# dev-board.net
KiCad netlist of a schematic drawn in EAGLE
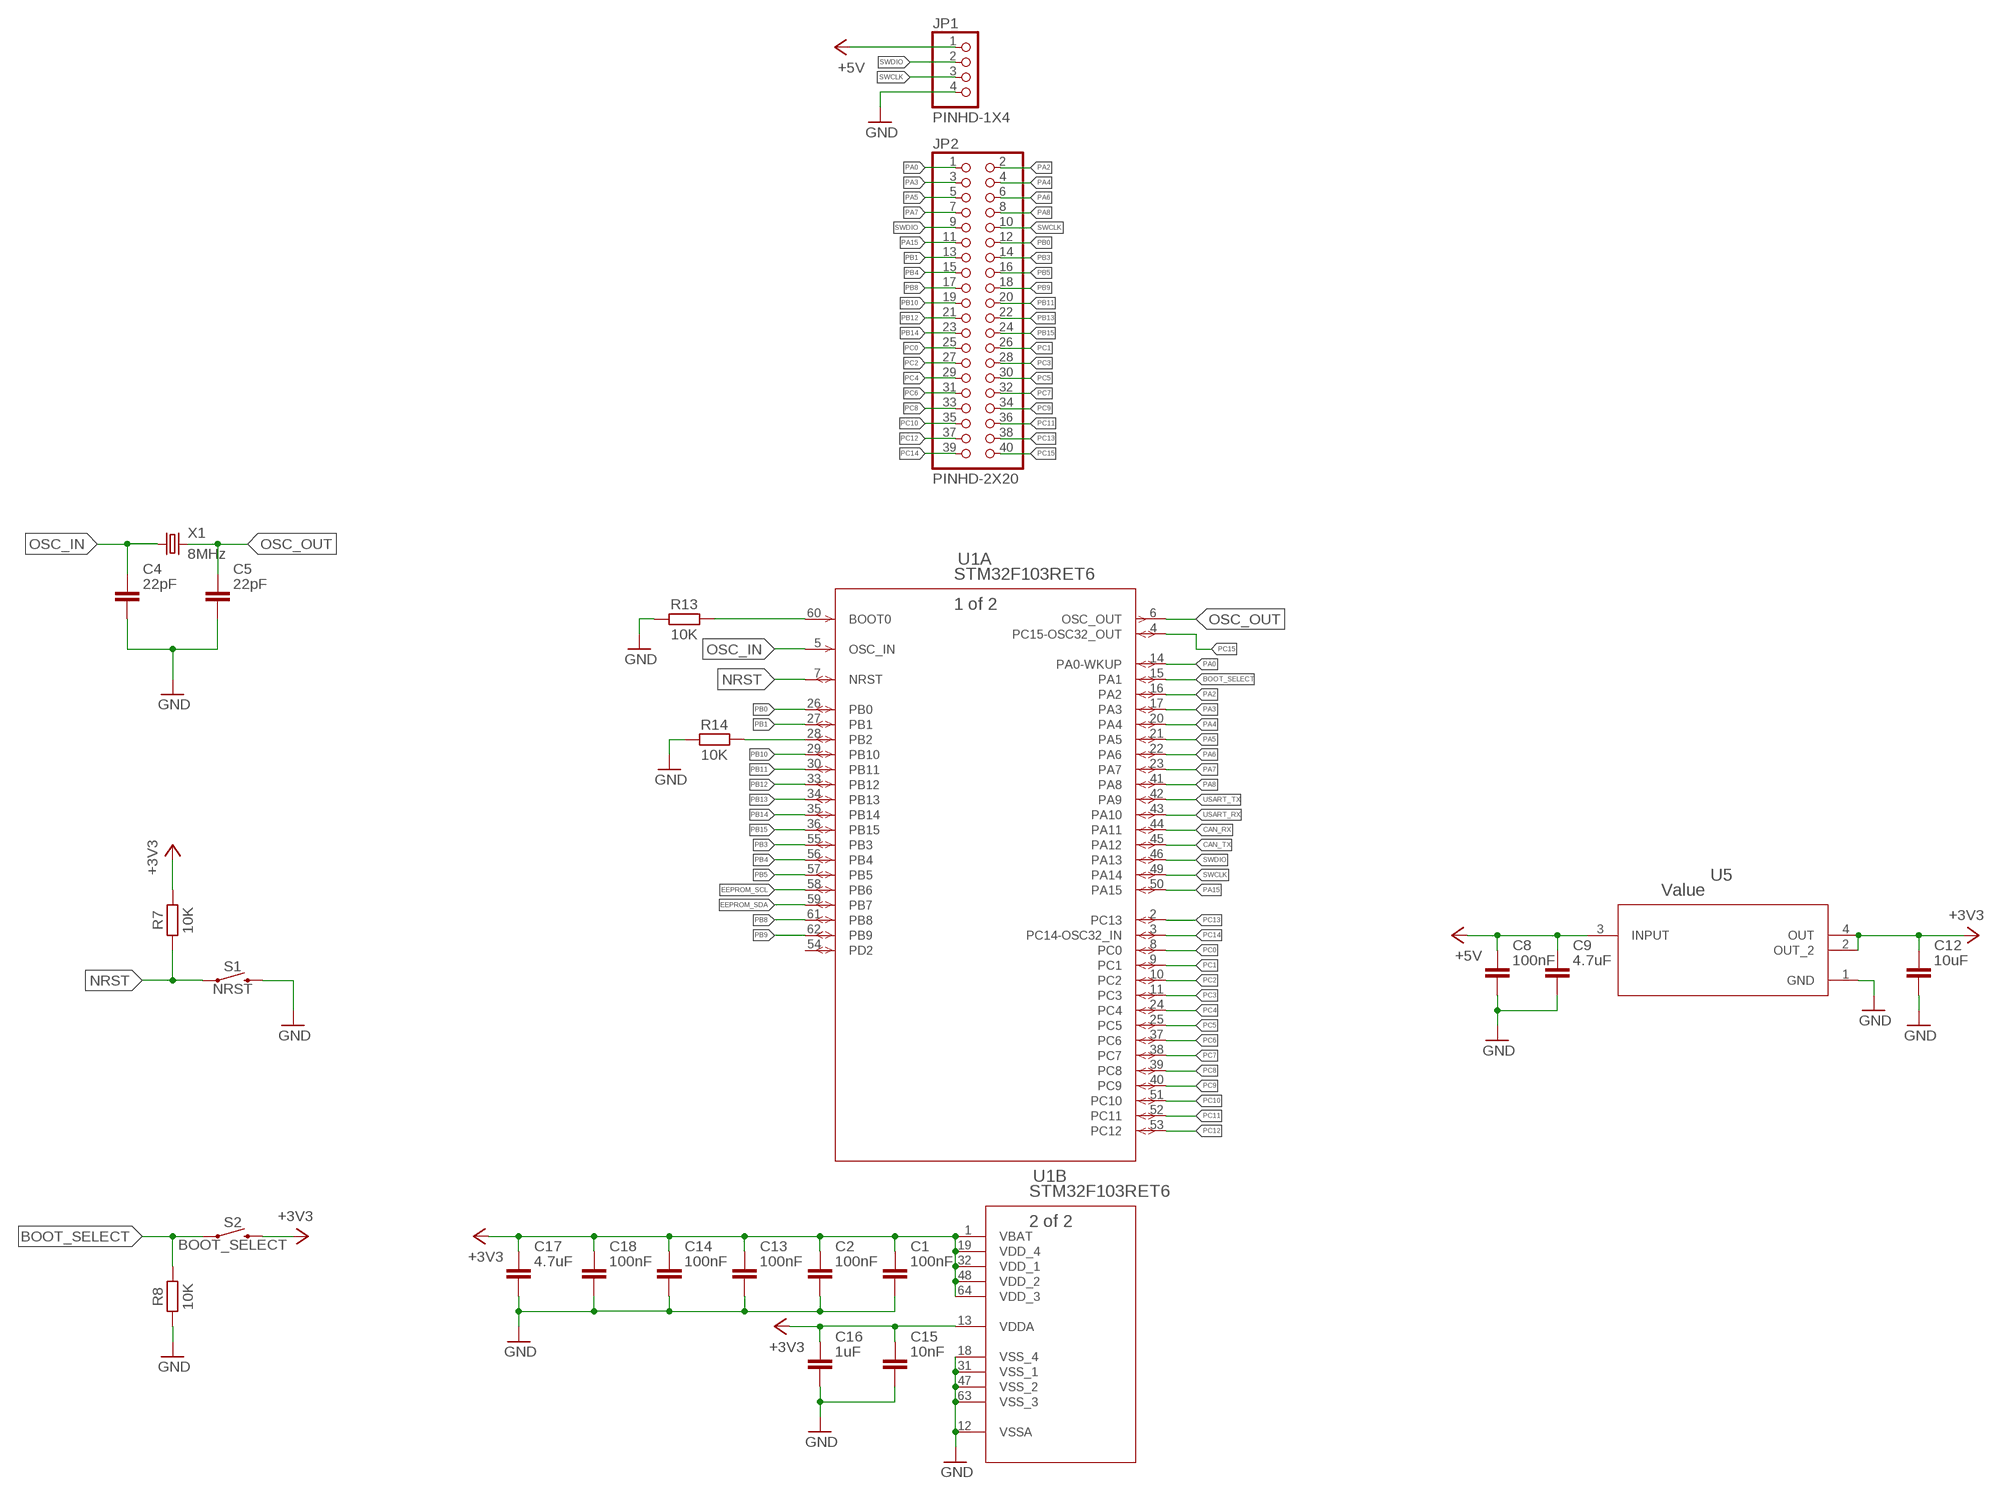
[diagram p0: schematic, sheet 1, part 1 of 2]
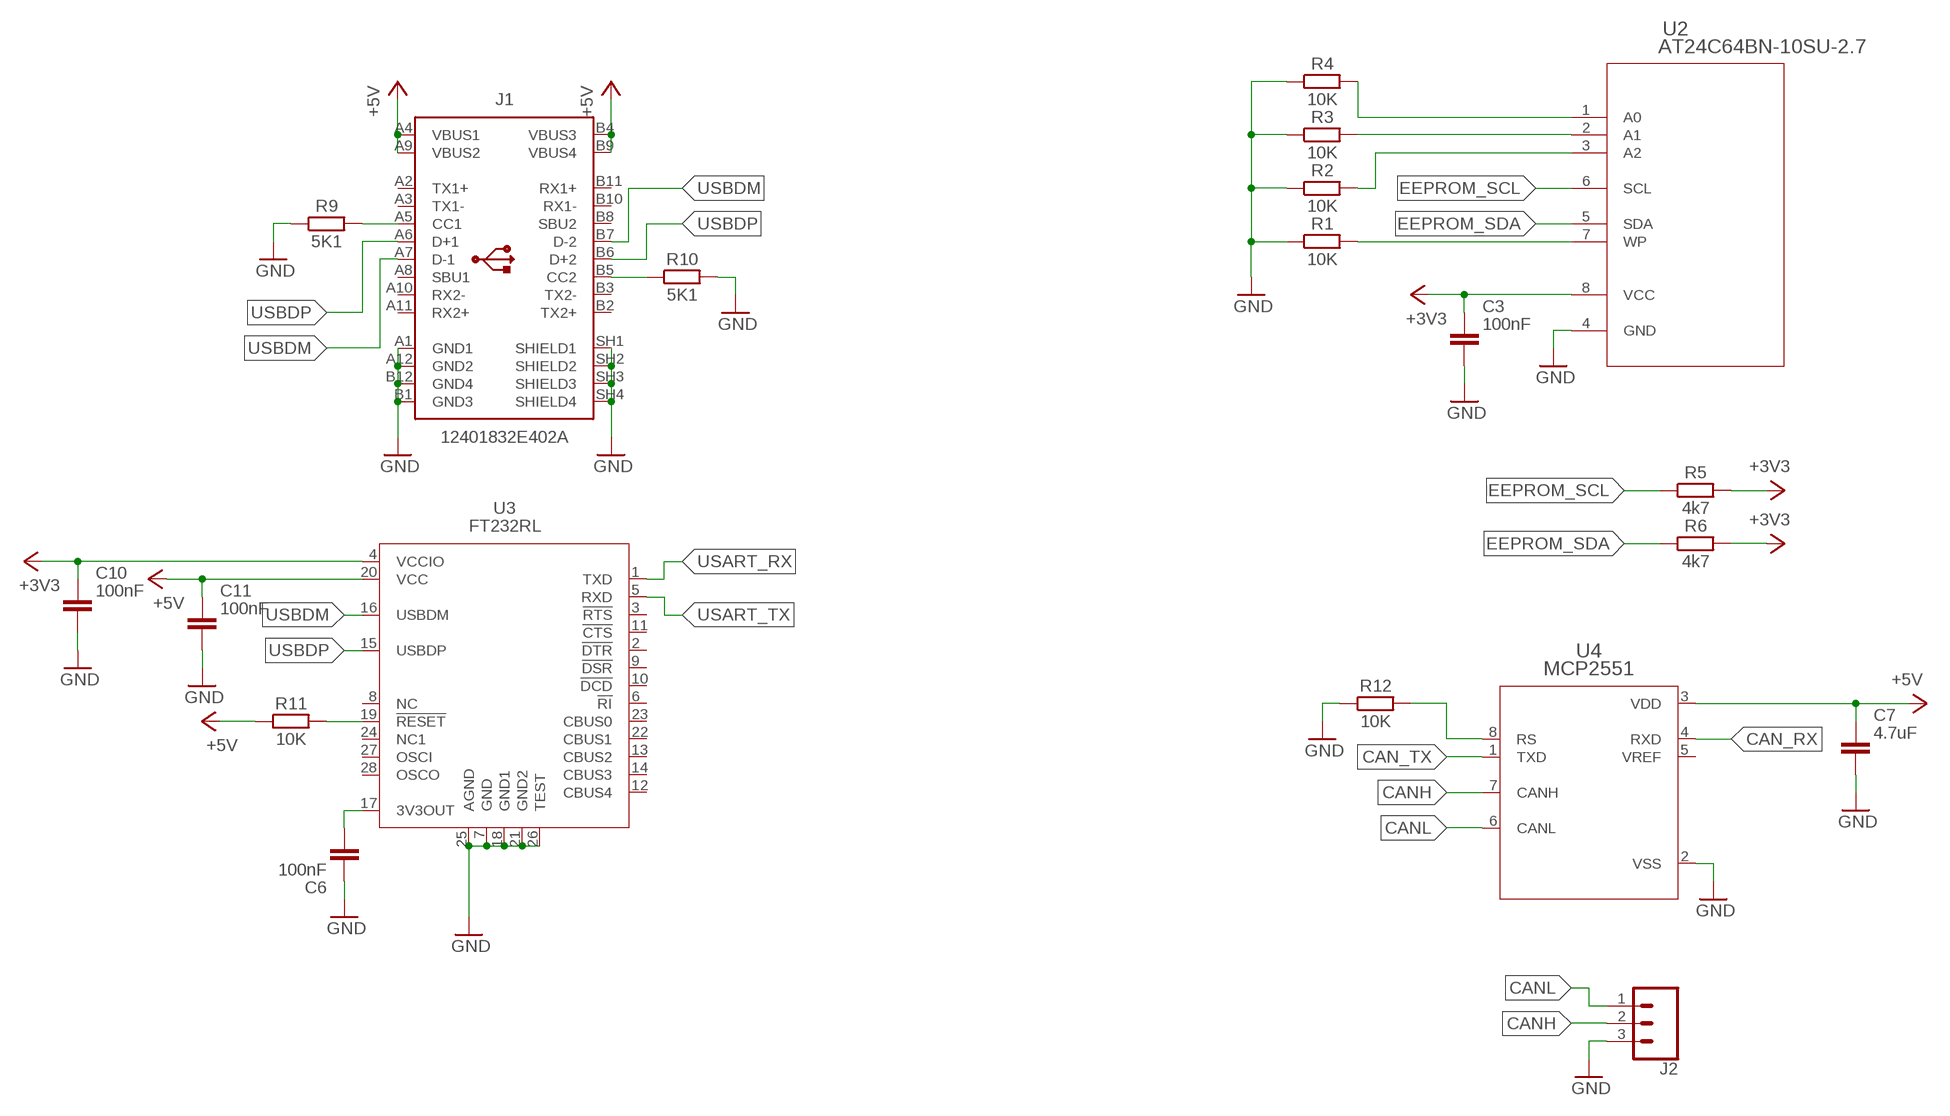
[diagram p1: schematic, sheet 1, part 2 of 2]

(export (version "E")
  (design (tool "Eeschema 10.0.6"))
  (components
    (comp (ref "C1")
      (value "100nF")
      (footprint "eagle-import:CAPC2012X110")
      (libsource (lib "eagle-import") (part "CCHIP-0805(2012-METRIC)_"))
    )
    (comp (ref "C2")
      (value "100nF")
      (footprint "eagle-import:CAPC2012X110")
      (libsource (lib "eagle-import") (part "CCHIP-0805(2012-METRIC)_"))
    )
    (comp (ref "C3")
      (value "100nF")
      (footprint "eagle-import:CAPC2012X110")
      (libsource (lib "eagle-import") (part "CCHIP-0805(2012-METRIC)_"))
    )
    (comp (ref "C4")
      (value "22pF")
      (footprint "eagle-import:CAPC2012X110")
      (libsource (lib "eagle-import") (part "CCHIP-0805(2012-METRIC)_"))
    )
    (comp (ref "C5")
      (value "22pF")
      (footprint "eagle-import:CAPC2012X110")
      (libsource (lib "eagle-import") (part "CCHIP-0805(2012-METRIC)_"))
    )
    (comp (ref "C6")
      (value "100nF")
      (footprint "eagle-import:CAPC2012X110")
      (libsource (lib "eagle-import") (part "CCHIP-0805(2012-METRIC)_"))
    )
    (comp (ref "C7")
      (value "4.7uF")
      (footprint "eagle-import:CAPC2012X110")
      (libsource (lib "eagle-import") (part "CCHIP-0805(2012-METRIC)_"))
    )
    (comp (ref "C8")
      (value "100nF")
      (footprint "eagle-import:CAPC2012X110")
      (libsource (lib "eagle-import") (part "CCHIP-0805(2012-METRIC)_"))
    )
    (comp (ref "C9")
      (value "4.7uF")
      (footprint "eagle-import:CAPC2012X110")
      (libsource (lib "eagle-import") (part "CCHIP-0805(2012-METRIC)_"))
    )
    (comp (ref "C10")
      (value "100nF")
      (footprint "eagle-import:CAPC2012X110")
      (libsource (lib "eagle-import") (part "CCHIP-0805(2012-METRIC)_"))
    )
    (comp (ref "C11")
      (value "100nF")
      (footprint "eagle-import:CAPC2012X110")
      (libsource (lib "eagle-import") (part "CCHIP-0805(2012-METRIC)_"))
    )
    (comp (ref "C12")
      (value "10uF")
      (footprint "eagle-import:CAPC2012X110")
      (libsource (lib "eagle-import") (part "CCHIP-0805(2012-METRIC)_"))
    )
    (comp (ref "C13")
      (value "100nF")
      (footprint "eagle-import:CAPC2012X110")
      (libsource (lib "eagle-import") (part "CCHIP-0805(2012-METRIC)_"))
    )
    (comp (ref "C14")
      (value "100nF")
      (footprint "eagle-import:CAPC2012X110")
      (libsource (lib "eagle-import") (part "CCHIP-0805(2012-METRIC)_"))
    )
    (comp (ref "C15")
      (value "10nF")
      (footprint "eagle-import:CAPC2012X110")
      (libsource (lib "eagle-import") (part "CCHIP-0805(2012-METRIC)_"))
    )
    (comp (ref "C16")
      (value "1uF")
      (footprint "eagle-import:CAPC2012X110")
      (libsource (lib "eagle-import") (part "CCHIP-0805(2012-METRIC)_"))
    )
    (comp (ref "C17")
      (value "4.7uF")
      (footprint "eagle-import:CAPC2012X110")
      (libsource (lib "eagle-import") (part "CCHIP-0805(2012-METRIC)_"))
    )
    (comp (ref "C18")
      (value "100nF")
      (footprint "eagle-import:CAPC2012X110")
      (libsource (lib "eagle-import") (part "CCHIP-0805(2012-METRIC)_"))
    )
    (comp (ref "J1")
      (value "12401832E402A")
      (footprint "eagle-import:12401832E402A")
      (fields (field (name "MANUFACTURER") "Amphenol ICC"))
      (libsource (lib "eagle-import") (part "12401832E402A"))
    )
    (comp (ref "J2")
      (value "CONN_03-SCREW-5MM")
      (footprint "eagle-import:SCREWTERMINAL-5MM-3")
      (libsource (lib "eagle-import") (part "CONN_03-SCREW-5MM"))
    )
    (comp (ref "JP1")
      (value "PINHD-1X4")
      (footprint "eagle-import:1X04")
      (libsource (lib "eagle-import") (part "PINHD-1X4"))
    )
    (comp (ref "JP2")
      (value "PINHD-2X20")
      (footprint "eagle-import:2X20")
      (libsource (lib "eagle-import") (part "PINHD-2X20"))
    )
    (comp (ref "R1")
      (value "10K")
      (footprint "eagle-import:RESC2012X65")
      (libsource (lib "eagle-import") (part "RCHIP-0805(2012-METRIC)_"))
    )
    (comp (ref "R2")
      (value "10K")
      (footprint "eagle-import:RESC2012X65")
      (libsource (lib "eagle-import") (part "RCHIP-0805(2012-METRIC)_"))
    )
    (comp (ref "R3")
      (value "10K")
      (footprint "eagle-import:RESC2012X65")
      (libsource (lib "eagle-import") (part "RCHIP-0805(2012-METRIC)_"))
    )
    (comp (ref "R4")
      (value "10K")
      (footprint "eagle-import:RESC2012X65")
      (libsource (lib "eagle-import") (part "RCHIP-0805(2012-METRIC)_"))
    )
    (comp (ref "R5")
      (value "4k7")
      (footprint "eagle-import:RESC2012X65")
      (libsource (lib "eagle-import") (part "RCHIP-0805(2012-METRIC)_"))
    )
    (comp (ref "R6")
      (value "4k7")
      (footprint "eagle-import:RESC2012X65")
      (libsource (lib "eagle-import") (part "RCHIP-0805(2012-METRIC)_"))
    )
    (comp (ref "R7")
      (value "10K")
      (footprint "eagle-import:RESC2012X65")
      (libsource (lib "eagle-import") (part "RCHIP-0805(2012-METRIC)_"))
    )
    (comp (ref "R8")
      (value "10K")
      (footprint "eagle-import:RESC2012X65")
      (libsource (lib "eagle-import") (part "RCHIP-0805(2012-METRIC)_"))
    )
    (comp (ref "R9")
      (value "5K1")
      (footprint "eagle-import:RESC2012X65")
      (libsource (lib "eagle-import") (part "RCHIP-0805(2012-METRIC)_"))
    )
    (comp (ref "R10")
      (value "5K1")
      (footprint "eagle-import:RESC2012X65")
      (libsource (lib "eagle-import") (part "RCHIP-0805(2012-METRIC)_"))
    )
    (comp (ref "R11")
      (value "10K")
      (footprint "eagle-import:RESC2012X65")
      (libsource (lib "eagle-import") (part "RCHIP-0805(2012-METRIC)_"))
    )
    (comp (ref "R12")
      (value "10K")
      (footprint "eagle-import:RESC2012X65")
      (libsource (lib "eagle-import") (part "RCHIP-0805(2012-METRIC)_"))
    )
    (comp (ref "R13")
      (value "10K")
      (footprint "eagle-import:RESC2012X65")
      (libsource (lib "eagle-import") (part "RCHIP-0805(2012-METRIC)_"))
    )
    (comp (ref "R14")
      (value "10K")
      (footprint "eagle-import:RESC2012X65")
      (libsource (lib "eagle-import") (part "RCHIP-0805(2012-METRIC)_"))
    )
    (comp (ref "S1")
      (value "NRST")
      (footprint "eagle-import:TACTILE_SWITCH_SMD_6.0X3.5MM")
      (libsource (lib "eagle-import") (part "MOMENTARY-SWITCH-SPST-SMD-6.0X3.5MM"))
    )
    (comp (ref "S2")
      (value "BOOT_SELECT")
      (footprint "eagle-import:TACTILE_SWITCH_SMD_6.0X3.5MM")
      (libsource (lib "eagle-import") (part "MOMENTARY-SWITCH-SPST-SMD-6.0X3.5MM"))
    )
    (comp (ref "U1")
      (value "STM32F103RET6")
      (footprint "eagle-import:LQFP64-10X10MM")
      (fields (field (name "COPYRIGHT") "Copyright (C) 2018 Accelerated Designs. All rights reserved"))
      (libsource (lib "eagle-import") (part "STM32F103RET6"))
    )
    (comp (ref "U2")
      (value "AT24C64BN-10SU-2.7")
      (footprint "eagle-import:8S1_ATM")
      (libsource (lib "eagle-import") (part "AT24C64BN-10SU-2.7"))
    )
    (comp (ref "U3")
      (value "FT232RL")
      (footprint "eagle-import:SSOP28")
      (fields (field (name "MANUFACTURER") "FTDI Chip"))
      (libsource (lib "eagle-import") (part "FT232RL_SSOP"))
    )
    (comp (ref "U4")
      (value "MCP2551")
      (footprint "eagle-import:SOIC127P599X175-8")
      (fields (field (name "MANUFACTURER") "Microchip") (field (name "MPN") "MCP2551-E/SN"))
      (libsource (lib "eagle-import") (part "MCP2551_SOIC"))
    )
    (comp (ref "U5")
      (value "Value")
      (footprint "eagle-import:DCY0004A_N")
      (fields
        (field (name "MANUFACTURER") "Texas Instruments")
        (field (name "PARTNUMBER") "LM1117IMP-3.3/NOPB")
      )
      (libsource (lib "eagle-import") (part "LM1117IMP-3.3/NOPB"))
    )
    (comp (ref "X1")
      (value "8MHz")
      (footprint "eagle-import:HC49-4-HSMX")
      (libsource (lib "eagle-import") (part "CRYSTALS-NOGND-4-HSMX"))
    )
  )
  (nets
    (net (code "1") (name "+3V3") (class "Default")
      (node (ref "C1") (pin "1") (pinfunction "1_1") (pintype "passive"))
      (node (ref "C10") (pin "1") (pinfunction "1_1") (pintype "passive"))
      (node (ref "C12") (pin "1") (pinfunction "1_1") (pintype "passive"))
      (node (ref "C13") (pin "1") (pinfunction "1_1") (pintype "passive"))
      (node (ref "C14") (pin "1") (pinfunction "1_1") (pintype "passive"))
      (node (ref "C15") (pin "1") (pinfunction "1_1") (pintype "passive"))
      (node (ref "C16") (pin "1") (pinfunction "1_1") (pintype "passive"))
      (node (ref "C17") (pin "1") (pinfunction "1_1") (pintype "passive"))
      (node (ref "C18") (pin "1") (pinfunction "1_1") (pintype "passive"))
      (node (ref "C2") (pin "1") (pinfunction "1_1") (pintype "passive"))
      (node (ref "C3") (pin "1") (pinfunction "1_1") (pintype "passive"))
      (node (ref "R5") (pin "2") (pinfunction "2_2") (pintype "passive"))
      (node (ref "R6") (pin "2") (pinfunction "2_2") (pintype "passive"))
      (node (ref "R7") (pin "2") (pinfunction "2_2") (pintype "passive"))
      (node (ref "S2") (pin "2") (pinfunction "2_2") (pintype "passive"))
      (node (ref "U1") (pin "1") (pinfunction "VBAT_1") (pintype "power_in"))
      (node (ref "U1") (pin "13") (pinfunction "VDDA_13") (pintype "power_in"))
      (node (ref "U1") (pin "19") (pinfunction "VDD_4_19") (pintype "power_in"))
      (node (ref "U1") (pin "32") (pinfunction "VDD_1_32") (pintype "power_in"))
      (node (ref "U1") (pin "48") (pinfunction "VDD_2_48") (pintype "power_in"))
      (node (ref "U1") (pin "64") (pinfunction "VDD_3_64") (pintype "power_in"))
      (node (ref "U2") (pin "8") (pinfunction "VCC_8") (pintype "power_in"))
      (node (ref "U3") (pin "4") (pinfunction "VCCIO_4") (pintype "power_in"))
      (node (ref "U5") (pin "2") (pinfunction "OUT_2_2") (pintype "power_in"))
      (node (ref "U5") (pin "4") (pinfunction "OUT_4") (pintype "power_in"))
    )
    (net (code "2") (name "+5V") (class "Default")
      (node (ref "C11") (pin "1") (pinfunction "1_1") (pintype "passive"))
      (node (ref "C7") (pin "1") (pinfunction "1_1") (pintype "passive"))
      (node (ref "C8") (pin "1") (pinfunction "1_1") (pintype "passive"))
      (node (ref "C9") (pin "1") (pinfunction "1_1") (pintype "passive"))
      (node (ref "J1") (pin "A4") (pinfunction "VBUS1_A4") (pintype "power_in"))
      (node (ref "J1") (pin "A9") (pinfunction "VBUS2_A9") (pintype "power_in"))
      (node (ref "J1") (pin "B4") (pinfunction "VBUS3_B4") (pintype "power_in"))
      (node (ref "J1") (pin "B9") (pinfunction "VBUS4_B9") (pintype "power_in"))
      (node (ref "JP1") (pin "1") (pinfunction "1_1") (pintype "passive"))
      (node (ref "R11") (pin "1") (pinfunction "1_1") (pintype "passive"))
      (node (ref "U3") (pin "20") (pinfunction "VCC_20") (pintype "power_in"))
      (node (ref "U4") (pin "3") (pinfunction "VDD_3") (pintype "power_in"))
      (node (ref "U5") (pin "3") (pinfunction "INPUT_3") (pintype "power_in"))
    )
    (net (code "3") (name "BOOT_SELECT") (class "Default")
      (node (ref "R8") (pin "2") (pinfunction "2_2") (pintype "passive"))
      (node (ref "S2") (pin "1") (pinfunction "1_1") (pintype "passive"))
      (node (ref "U1") (pin "15") (pinfunction "PA1_15") (pintype "bidirectional"))
    )
    (net (code "4") (name "CANH") (class "Default")
      (node (ref "J2") (pin "2") (pinfunction "2_2") (pintype "passive"))
      (node (ref "U4") (pin "7") (pinfunction "CANH_7") (pintype "bidirectional"))
    )
    (net (code "5") (name "CANL") (class "Default")
      (node (ref "J2") (pin "1") (pinfunction "1_1") (pintype "passive"))
      (node (ref "U4") (pin "6") (pinfunction "CANL_6") (pintype "bidirectional"))
    )
    (net (code "6") (name "CAN_RX") (class "Default")
      (node (ref "U1") (pin "44") (pinfunction "PA11_44") (pintype "bidirectional"))
      (node (ref "U4") (pin "4") (pinfunction "RXD_4") (pintype "output"))
    )
    (net (code "7") (name "CAN_TX") (class "Default")
      (node (ref "U1") (pin "45") (pinfunction "PA12_45") (pintype "bidirectional"))
      (node (ref "U4") (pin "1") (pinfunction "TXD_1") (pintype "input"))
    )
    (net (code "8") (name "EEPROM_SCL") (class "Default")
      (node (ref "R5") (pin "1") (pinfunction "1_1") (pintype "passive"))
      (node (ref "U1") (pin "58") (pinfunction "PB6_58") (pintype "bidirectional"))
      (node (ref "U2") (pin "6") (pinfunction "SCL_6") (pintype "input"))
    )
    (net (code "9") (name "EEPROM_SDA") (class "Default")
      (node (ref "R6") (pin "1") (pinfunction "1_1") (pintype "passive"))
      (node (ref "U1") (pin "59") (pinfunction "PB7_59") (pintype "bidirectional"))
      (node (ref "U2") (pin "5") (pinfunction "SDA_5") (pintype "passive"))
    )
    (net (code "10") (name "GND") (class "Default")
      (node (ref "C1") (pin "2") (pinfunction "2_2") (pintype "passive"))
      (node (ref "C10") (pin "2") (pinfunction "2_2") (pintype "passive"))
      (node (ref "C11") (pin "2") (pinfunction "2_2") (pintype "passive"))
      (node (ref "C12") (pin "2") (pinfunction "2_2") (pintype "passive"))
      (node (ref "C13") (pin "2") (pinfunction "2_2") (pintype "passive"))
      (node (ref "C14") (pin "2") (pinfunction "2_2") (pintype "passive"))
      (node (ref "C15") (pin "2") (pinfunction "2_2") (pintype "passive"))
      (node (ref "C16") (pin "2") (pinfunction "2_2") (pintype "passive"))
      (node (ref "C17") (pin "2") (pinfunction "2_2") (pintype "passive"))
      (node (ref "C18") (pin "2") (pinfunction "2_2") (pintype "passive"))
      (node (ref "C2") (pin "2") (pinfunction "2_2") (pintype "passive"))
      (node (ref "C3") (pin "2") (pinfunction "2_2") (pintype "passive"))
      (node (ref "C4") (pin "2") (pinfunction "2_2") (pintype "passive"))
      (node (ref "C5") (pin "2") (pinfunction "2_2") (pintype "passive"))
      (node (ref "C6") (pin "1") (pinfunction "1_1") (pintype "passive"))
      (node (ref "C7") (pin "2") (pinfunction "2_2") (pintype "passive"))
      (node (ref "C8") (pin "2") (pinfunction "2_2") (pintype "passive"))
      (node (ref "C9") (pin "2") (pinfunction "2_2") (pintype "passive"))
      (node (ref "J1") (pin "A1") (pinfunction "GND1_A1") (pintype "power_in"))
      (node (ref "J1") (pin "A12") (pinfunction "GND2_A12") (pintype "power_in"))
      (node (ref "J1") (pin "B1") (pinfunction "GND3_B1") (pintype "power_in"))
      (node (ref "J1") (pin "B12") (pinfunction "GND4_B12") (pintype "power_in"))
      (node (ref "J1") (pin "SH1") (pinfunction "SHIELD1_SH1") (pintype "power_in"))
      (node (ref "J1") (pin "SH2") (pinfunction "SHIELD2_SH2") (pintype "power_in"))
      (node (ref "J1") (pin "SH3") (pinfunction "SHIELD3_SH3") (pintype "power_in"))
      (node (ref "J1") (pin "SH4") (pinfunction "SHIELD4_SH4") (pintype "power_in"))
      (node (ref "J2") (pin "3") (pinfunction "3_3") (pintype "passive"))
      (node (ref "JP1") (pin "4") (pinfunction "4_4") (pintype "passive"))
      (node (ref "R1") (pin "1") (pinfunction "1_1") (pintype "passive"))
      (node (ref "R10") (pin "2") (pinfunction "2_2") (pintype "passive"))
      (node (ref "R12") (pin "1") (pinfunction "1_1") (pintype "passive"))
      (node (ref "R13") (pin "1") (pinfunction "1_1") (pintype "passive"))
      (node (ref "R14") (pin "1") (pinfunction "1_1") (pintype "passive"))
      (node (ref "R2") (pin "1") (pinfunction "1_1") (pintype "passive"))
      (node (ref "R3") (pin "1") (pinfunction "1_1") (pintype "passive"))
      (node (ref "R4") (pin "1") (pinfunction "1_1") (pintype "passive"))
      (node (ref "R8") (pin "1") (pinfunction "1_1") (pintype "passive"))
      (node (ref "R9") (pin "1") (pinfunction "1_1") (pintype "passive"))
      (node (ref "S1") (pin "2") (pinfunction "2_2") (pintype "passive"))
      (node (ref "U1") (pin "12") (pinfunction "VSSA_12") (pintype "power_in"))
      (node (ref "U1") (pin "18") (pinfunction "VSS_4_18") (pintype "power_in"))
      (node (ref "U1") (pin "31") (pinfunction "VSS_1_31") (pintype "power_in"))
      (node (ref "U1") (pin "47") (pinfunction "VSS_2_47") (pintype "power_in"))
      (node (ref "U1") (pin "63") (pinfunction "VSS_3_63") (pintype "power_in"))
      (node (ref "U2") (pin "4") (pinfunction "GND_4") (pintype "power_in"))
      (node (ref "U3") (pin "18") (pinfunction "GND1_18") (pintype "power_in"))
      (node (ref "U3") (pin "21") (pinfunction "GND2_21") (pintype "power_in"))
      (node (ref "U3") (pin "25") (pinfunction "AGND_25") (pintype "power_in"))
      (node (ref "U3") (pin "26") (pinfunction "TEST_26") (pintype "input"))
      (node (ref "U3") (pin "7") (pinfunction "GND_7") (pintype "power_in"))
      (node (ref "U4") (pin "2") (pinfunction "VSS_2") (pintype "power_in"))
      (node (ref "U5") (pin "1") (pinfunction "GND_1") (pintype "power_in"))
    )
    (net (code "11") (name "NRST") (class "Default")
      (node (ref "R7") (pin "1") (pinfunction "1_1") (pintype "passive"))
      (node (ref "S1") (pin "1") (pinfunction "1_1") (pintype "passive"))
      (node (ref "U1") (pin "7") (pinfunction "NRST_7") (pintype "bidirectional"))
    )
    (net (code "12") (name "Net-(J1-CC1)") (class "Default")
      (node (ref "J1") (pin "A5") (pinfunction "CC1_A5") (pintype "bidirectional"))
      (node (ref "R9") (pin "2") (pinfunction "2_2") (pintype "passive"))
    )
    (net (code "13") (name "Net-(J1-CC2)") (class "Default")
      (node (ref "J1") (pin "B5") (pinfunction "CC2_B5") (pintype "bidirectional"))
      (node (ref "R10") (pin "1") (pinfunction "1_1") (pintype "passive"))
    )
    (net (code "14") (name "Net-(U1A-BOOT0)") (class "Default")
      (node (ref "R13") (pin "2") (pinfunction "2_2") (pintype "passive"))
      (node (ref "U1") (pin "60") (pinfunction "BOOT0_60") (pintype "input"))
    )
    (net (code "15") (name "Net-(U1A-PB2)") (class "Default")
      (node (ref "R14") (pin "2") (pinfunction "2_2") (pintype "passive"))
      (node (ref "U1") (pin "28") (pinfunction "PB2_28") (pintype "bidirectional"))
    )
    (net (code "16") (name "Net-(U2-A0)") (class "Default")
      (node (ref "R4") (pin "2") (pinfunction "2_2") (pintype "passive"))
      (node (ref "U2") (pin "1") (pinfunction "A0_1") (pintype "input"))
    )
    (net (code "17") (name "Net-(U2-A1)") (class "Default")
      (node (ref "R3") (pin "2") (pinfunction "2_2") (pintype "passive"))
      (node (ref "U2") (pin "2") (pinfunction "A1_2") (pintype "input"))
    )
    (net (code "18") (name "Net-(U2-A2)") (class "Default")
      (node (ref "R2") (pin "2") (pinfunction "2_2") (pintype "passive"))
      (node (ref "U2") (pin "3") (pinfunction "A2_3") (pintype "input"))
    )
    (net (code "19") (name "Net-(U2-WP)") (class "Default")
      (node (ref "R1") (pin "2") (pinfunction "2_2") (pintype "passive"))
      (node (ref "U2") (pin "7") (pinfunction "WP_7") (pintype "passive"))
    )
    (net (code "20") (name "Net-(U3-3V3OUT)") (class "Default")
      (node (ref "C6") (pin "2") (pinfunction "2_2") (pintype "passive"))
      (node (ref "U3") (pin "17") (pinfunction "3V3OUT_17") (pintype "output"))
    )
    (net (code "21") (name "Net-(U3-~{RESET})") (class "Default")
      (node (ref "R11") (pin "2") (pinfunction "2_2") (pintype "passive"))
      (node (ref "U3") (pin "19") (pinfunction "~{RESET}_19") (pintype "input"))
    )
    (net (code "22") (name "Net-(U4-RS)") (class "Default")
      (node (ref "R12") (pin "2") (pinfunction "2_2") (pintype "passive"))
      (node (ref "U4") (pin "8") (pinfunction "RS_8") (pintype "input"))
    )
    (net (code "23") (name "OSC_IN") (class "Default")
      (node (ref "C4") (pin "1") (pinfunction "1_1") (pintype "passive"))
      (node (ref "U1") (pin "5") (pinfunction "OSC_IN_5") (pintype "input"))
      (node (ref "X1") (pin "1") (pinfunction "1_1") (pintype "passive"))
    )
    (net (code "24") (name "OSC_OUT") (class "Default")
      (node (ref "C5") (pin "1") (pinfunction "1_1") (pintype "passive"))
      (node (ref "U1") (pin "6") (pinfunction "OSC_OUT_6") (pintype "output"))
      (node (ref "X1") (pin "2") (pinfunction "2_2") (pintype "passive"))
    )
    (net (code "25") (name "PA0") (class "Default")
      (node (ref "JP2") (pin "1") (pinfunction "1_1") (pintype "passive"))
      (node (ref "U1") (pin "14") (pinfunction "PA0-WKUP_14") (pintype "bidirectional"))
    )
    (net (code "26") (name "PA2") (class "Default")
      (node (ref "JP2") (pin "2") (pinfunction "2_2") (pintype "passive"))
      (node (ref "U1") (pin "16") (pinfunction "PA2_16") (pintype "bidirectional"))
    )
    (net (code "27") (name "PA3") (class "Default")
      (node (ref "JP2") (pin "3") (pinfunction "3_3") (pintype "passive"))
      (node (ref "U1") (pin "17") (pinfunction "PA3_17") (pintype "bidirectional"))
    )
    (net (code "28") (name "PA4") (class "Default")
      (node (ref "JP2") (pin "4") (pinfunction "4_4") (pintype "passive"))
      (node (ref "U1") (pin "20") (pinfunction "PA4_20") (pintype "bidirectional"))
    )
    (net (code "29") (name "PA5") (class "Default")
      (node (ref "JP2") (pin "5") (pinfunction "5_5") (pintype "passive"))
      (node (ref "U1") (pin "21") (pinfunction "PA5_21") (pintype "bidirectional"))
    )
    (net (code "30") (name "PA6") (class "Default")
      (node (ref "JP2") (pin "6") (pinfunction "6_6") (pintype "passive"))
      (node (ref "U1") (pin "22") (pinfunction "PA6_22") (pintype "bidirectional"))
    )
    (net (code "31") (name "PA7") (class "Default")
      (node (ref "JP2") (pin "7") (pinfunction "7_7") (pintype "passive"))
      (node (ref "U1") (pin "23") (pinfunction "PA7_23") (pintype "bidirectional"))
    )
    (net (code "32") (name "PA8") (class "Default")
      (node (ref "JP2") (pin "8") (pinfunction "8_8") (pintype "passive"))
      (node (ref "U1") (pin "41") (pinfunction "PA8_41") (pintype "bidirectional"))
    )
    (net (code "33") (name "PA15") (class "Default")
      (node (ref "JP2") (pin "11") (pinfunction "11_11") (pintype "passive"))
      (node (ref "U1") (pin "50") (pinfunction "PA15_50") (pintype "bidirectional"))
    )
    (net (code "34") (name "PB0") (class "Default")
      (node (ref "JP2") (pin "12") (pinfunction "12_12") (pintype "passive"))
      (node (ref "U1") (pin "26") (pinfunction "PB0_26") (pintype "bidirectional"))
    )
    (net (code "35") (name "PB1") (class "Default")
      (node (ref "JP2") (pin "13") (pinfunction "13_13") (pintype "passive"))
      (node (ref "U1") (pin "27") (pinfunction "PB1_27") (pintype "bidirectional"))
    )
    (net (code "36") (name "PB3") (class "Default")
      (node (ref "JP2") (pin "14") (pinfunction "14_14") (pintype "passive"))
      (node (ref "U1") (pin "55") (pinfunction "PB3_55") (pintype "bidirectional"))
    )
    (net (code "37") (name "PB4") (class "Default")
      (node (ref "JP2") (pin "15") (pinfunction "15_15") (pintype "passive"))
      (node (ref "U1") (pin "56") (pinfunction "PB4_56") (pintype "bidirectional"))
    )
    (net (code "38") (name "PB5") (class "Default")
      (node (ref "JP2") (pin "16") (pinfunction "16_16") (pintype "passive"))
      (node (ref "U1") (pin "57") (pinfunction "PB5_57") (pintype "bidirectional"))
    )
    (net (code "39") (name "PB8") (class "Default")
      (node (ref "JP2") (pin "17") (pinfunction "17_17") (pintype "passive"))
      (node (ref "U1") (pin "61") (pinfunction "PB8_61") (pintype "bidirectional"))
    )
    (net (code "40") (name "PB9") (class "Default")
      (node (ref "JP2") (pin "18") (pinfunction "18_18") (pintype "passive"))
      (node (ref "U1") (pin "62") (pinfunction "PB9_62") (pintype "bidirectional"))
    )
    (net (code "41") (name "PB10") (class "Default")
      (node (ref "JP2") (pin "19") (pinfunction "19_19") (pintype "passive"))
      (node (ref "U1") (pin "29") (pinfunction "PB10_29") (pintype "bidirectional"))
    )
    (net (code "42") (name "PB11") (class "Default")
      (node (ref "JP2") (pin "20") (pinfunction "20_20") (pintype "passive"))
      (node (ref "U1") (pin "30") (pinfunction "PB11_30") (pintype "bidirectional"))
    )
    (net (code "43") (name "PB12") (class "Default")
      (node (ref "JP2") (pin "21") (pinfunction "21_21") (pintype "passive"))
      (node (ref "U1") (pin "33") (pinfunction "PB12_33") (pintype "bidirectional"))
    )
    (net (code "44") (name "PB13") (class "Default")
      (node (ref "JP2") (pin "22") (pinfunction "22_22") (pintype "passive"))
      (node (ref "U1") (pin "34") (pinfunction "PB13_34") (pintype "bidirectional"))
    )
    (net (code "45") (name "PB14") (class "Default")
      (node (ref "JP2") (pin "23") (pinfunction "23_23") (pintype "passive"))
      (node (ref "U1") (pin "35") (pinfunction "PB14_35") (pintype "bidirectional"))
    )
    (net (code "46") (name "PB15") (class "Default")
      (node (ref "JP2") (pin "24") (pinfunction "24_24") (pintype "passive"))
      (node (ref "U1") (pin "36") (pinfunction "PB15_36") (pintype "bidirectional"))
    )
    (net (code "47") (name "PC0") (class "Default")
      (node (ref "JP2") (pin "25") (pinfunction "25_25") (pintype "passive"))
      (node (ref "U1") (pin "8") (pinfunction "PC0_8") (pintype "bidirectional"))
    )
    (net (code "48") (name "PC1") (class "Default")
      (node (ref "JP2") (pin "26") (pinfunction "26_26") (pintype "passive"))
      (node (ref "U1") (pin "9") (pinfunction "PC1_9") (pintype "bidirectional"))
    )
    (net (code "49") (name "PC2") (class "Default")
      (node (ref "JP2") (pin "27") (pinfunction "27_27") (pintype "passive"))
      (node (ref "U1") (pin "10") (pinfunction "PC2_10") (pintype "bidirectional"))
    )
    (net (code "50") (name "PC3") (class "Default")
      (node (ref "JP2") (pin "28") (pinfunction "28_28") (pintype "passive"))
      (node (ref "U1") (pin "11") (pinfunction "PC3_11") (pintype "bidirectional"))
    )
    (net (code "51") (name "PC4") (class "Default")
      (node (ref "JP2") (pin "29") (pinfunction "29_29") (pintype "passive"))
      (node (ref "U1") (pin "24") (pinfunction "PC4_24") (pintype "bidirectional"))
    )
    (net (code "52") (name "PC5") (class "Default")
      (node (ref "JP2") (pin "30") (pinfunction "30_30") (pintype "passive"))
      (node (ref "U1") (pin "25") (pinfunction "PC5_25") (pintype "bidirectional"))
    )
    (net (code "53") (name "PC6") (class "Default")
      (node (ref "JP2") (pin "31") (pinfunction "31_31") (pintype "passive"))
      (node (ref "U1") (pin "37") (pinfunction "PC6_37") (pintype "bidirectional"))
    )
    (net (code "54") (name "PC7") (class "Default")
      (node (ref "JP2") (pin "32") (pinfunction "32_32") (pintype "passive"))
      (node (ref "U1") (pin "38") (pinfunction "PC7_38") (pintype "bidirectional"))
    )
    (net (code "55") (name "PC8") (class "Default")
      (node (ref "JP2") (pin "33") (pinfunction "33_33") (pintype "passive"))
      (node (ref "U1") (pin "39") (pinfunction "PC8_39") (pintype "bidirectional"))
    )
    (net (code "56") (name "PC9") (class "Default")
      (node (ref "JP2") (pin "34") (pinfunction "34_34") (pintype "passive"))
      (node (ref "U1") (pin "40") (pinfunction "PC9_40") (pintype "bidirectional"))
    )
    (net (code "57") (name "PC10") (class "Default")
      (node (ref "JP2") (pin "35") (pinfunction "35_35") (pintype "passive"))
      (node (ref "U1") (pin "51") (pinfunction "PC10_51") (pintype "bidirectional"))
    )
    (net (code "58") (name "PC11") (class "Default")
      (node (ref "JP2") (pin "36") (pinfunction "36_36") (pintype "passive"))
      (node (ref "U1") (pin "52") (pinfunction "PC11_52") (pintype "bidirectional"))
    )
    (net (code "59") (name "PC12") (class "Default")
      (node (ref "JP2") (pin "37") (pinfunction "37_37") (pintype "passive"))
      (node (ref "U1") (pin "53") (pinfunction "PC12_53") (pintype "bidirectional"))
    )
    (net (code "60") (name "PC13") (class "Default")
      (node (ref "JP2") (pin "38") (pinfunction "38_38") (pintype "passive"))
      (node (ref "U1") (pin "2") (pinfunction "PC13_2") (pintype "bidirectional"))
    )
    (net (code "61") (name "PC14") (class "Default")
      (node (ref "JP2") (pin "39") (pinfunction "39_39") (pintype "passive"))
      (node (ref "U1") (pin "3") (pinfunction "PC14-OSC32_IN_3") (pintype "bidirectional"))
    )
    (net (code "62") (name "PC15") (class "Default")
      (node (ref "JP2") (pin "40") (pinfunction "40_40") (pintype "passive"))
      (node (ref "U1") (pin "4") (pinfunction "PC15-OSC32_OUT_4") (pintype "bidirectional"))
    )
    (net (code "63") (name "SWCLK") (class "Default")
      (node (ref "JP1") (pin "3") (pinfunction "3_3") (pintype "passive"))
      (node (ref "JP2") (pin "10") (pinfunction "10_10") (pintype "passive"))
      (node (ref "U1") (pin "49") (pinfunction "PA14_49") (pintype "bidirectional"))
    )
    (net (code "64") (name "SWDIO") (class "Default")
      (node (ref "JP1") (pin "2") (pinfunction "2_2") (pintype "passive"))
      (node (ref "JP2") (pin "9") (pinfunction "9_9") (pintype "passive"))
      (node (ref "U1") (pin "46") (pinfunction "PA13_46") (pintype "bidirectional"))
    )
    (net (code "65") (name "USART_RX") (class "Default")
      (node (ref "U1") (pin "43") (pinfunction "PA10_43") (pintype "bidirectional"))
      (node (ref "U3") (pin "1") (pinfunction "TXD_1") (pintype "output"))
    )
    (net (code "66") (name "USART_TX") (class "Default")
      (node (ref "U1") (pin "42") (pinfunction "PA9_42") (pintype "bidirectional"))
      (node (ref "U3") (pin "5") (pinfunction "RXD_5") (pintype "input"))
    )
    (net (code "67") (name "USBDM") (class "Default")
      (node (ref "J1") (pin "A7") (pinfunction "D-1_A7") (pintype "bidirectional"))
      (node (ref "J1") (pin "B7") (pinfunction "D-2_B7") (pintype "bidirectional"))
      (node (ref "U3") (pin "16") (pinfunction "USBDM_16") (pintype "bidirectional"))
    )
    (net (code "68") (name "USBDP") (class "Default")
      (node (ref "J1") (pin "A6") (pinfunction "D+1_A6") (pintype "bidirectional"))
      (node (ref "J1") (pin "B6") (pinfunction "D+2_B6") (pintype "bidirectional"))
      (node (ref "U3") (pin "15") (pinfunction "USBDP_15") (pintype "bidirectional"))
    )
    (net (code "69") (name "unconnected-(J1-RX1+-PadB11)") (class "Default")
      (node (ref "J1") (pin "B11") (pinfunction "RX1+_B11") (pintype "bidirectional"))
    )
    (net (code "70") (name "unconnected-(J1-RX1--PadB10)") (class "Default")
      (node (ref "J1") (pin "B10") (pinfunction "RX1-_B10") (pintype "bidirectional"))
    )
    (net (code "71") (name "unconnected-(J1-RX2+-PadA11)") (class "Default")
      (node (ref "J1") (pin "A11") (pinfunction "RX2+_A11") (pintype "bidirectional"))
    )
    (net (code "72") (name "unconnected-(J1-RX2--PadA10)") (class "Default")
      (node (ref "J1") (pin "A10") (pinfunction "RX2-_A10") (pintype "bidirectional"))
    )
    (net (code "73") (name "unconnected-(J1-SBU1-PadA8)") (class "Default")
      (node (ref "J1") (pin "A8") (pinfunction "SBU1_A8") (pintype "bidirectional"))
    )
    (net (code "74") (name "unconnected-(J1-SBU2-PadB8)") (class "Default")
      (node (ref "J1") (pin "B8") (pinfunction "SBU2_B8") (pintype "bidirectional"))
    )
    (net (code "75") (name "unconnected-(J1-TX1+-PadA2)") (class "Default")
      (node (ref "J1") (pin "A2") (pinfunction "TX1+_A2") (pintype "bidirectional"))
    )
    (net (code "76") (name "unconnected-(J1-TX1--PadA3)") (class "Default")
      (node (ref "J1") (pin "A3") (pinfunction "TX1-_A3") (pintype "bidirectional"))
    )
    (net (code "77") (name "unconnected-(J1-TX2+-PadB2)") (class "Default")
      (node (ref "J1") (pin "B2") (pinfunction "TX2+_B2") (pintype "bidirectional"))
    )
    (net (code "78") (name "unconnected-(J1-TX2--PadB3)") (class "Default")
      (node (ref "J1") (pin "B3") (pinfunction "TX2-_B3") (pintype "bidirectional"))
    )
    (net (code "79") (name "unconnected-(U1A-PD2-Pad54)") (class "Default")
      (node (ref "U1") (pin "54") (pinfunction "PD2_54") (pintype "bidirectional"))
    )
    (net (code "80") (name "unconnected-(U3-CBUS0-Pad23)") (class "Default")
      (node (ref "U3") (pin "23") (pinfunction "CBUS0_23") (pintype "bidirectional"))
    )
    (net (code "81") (name "unconnected-(U3-CBUS1-Pad22)") (class "Default")
      (node (ref "U3") (pin "22") (pinfunction "CBUS1_22") (pintype "bidirectional"))
    )
    (net (code "82") (name "unconnected-(U3-CBUS2-Pad13)") (class "Default")
      (node (ref "U3") (pin "13") (pinfunction "CBUS2_13") (pintype "bidirectional"))
    )
    (net (code "83") (name "unconnected-(U3-CBUS3-Pad14)") (class "Default")
      (node (ref "U3") (pin "14") (pinfunction "CBUS3_14") (pintype "bidirectional"))
    )
    (net (code "84") (name "unconnected-(U3-CBUS4-Pad12)") (class "Default")
      (node (ref "U3") (pin "12") (pinfunction "CBUS4_12") (pintype "bidirectional"))
    )
    (net (code "85") (name "unconnected-(U3-NC-Pad8)") (class "Default")
      (node (ref "U3") (pin "8") (pinfunction "NC_8") (pintype "no_connect"))
    )
    (net (code "86") (name "unconnected-(U3-NC1-Pad24)") (class "Default")
      (node (ref "U3") (pin "24") (pinfunction "NC1_24") (pintype "no_connect"))
    )
    (net (code "87") (name "unconnected-(U3-OSCI-Pad27)") (class "Default")
      (node (ref "U3") (pin "27") (pinfunction "OSCI_27") (pintype "input"))
    )
    (net (code "88") (name "unconnected-(U3-OSCO-Pad28)") (class "Default")
      (node (ref "U3") (pin "28") (pinfunction "OSCO_28") (pintype "input"))
    )
    (net (code "89") (name "unconnected-(U3-~{CTS}-Pad11)") (class "Default")
      (node (ref "U3") (pin "11") (pinfunction "~{CTS}_11") (pintype "input"))
    )
    (net (code "90") (name "unconnected-(U3-~{DCD}-Pad10)") (class "Default")
      (node (ref "U3") (pin "10") (pinfunction "~{DCD}_10") (pintype "input"))
    )
    (net (code "91") (name "unconnected-(U3-~{DSR}-Pad9)") (class "Default")
      (node (ref "U3") (pin "9") (pinfunction "~{DSR}_9") (pintype "input"))
    )
    (net (code "92") (name "unconnected-(U3-~{DTR}-Pad2)") (class "Default")
      (node (ref "U3") (pin "2") (pinfunction "~{DTR}_2") (pintype "output"))
    )
    (net (code "93") (name "unconnected-(U3-~{RI}-Pad6)") (class "Default")
      (node (ref "U3") (pin "6") (pinfunction "~{RI}_6") (pintype "input"))
    )
    (net (code "94") (name "unconnected-(U3-~{RTS}-Pad3)") (class "Default")
      (node (ref "U3") (pin "3") (pinfunction "~{RTS}_3") (pintype "output"))
    )
    (net (code "95") (name "unconnected-(U4-VREF-Pad5)") (class "Default")
      (node (ref "U4") (pin "5") (pinfunction "VREF_5") (pintype "output"))
    )
  )
)
